# NavCom_Board_3.net
KiCad netlist of a schematic drawn in EAGLE
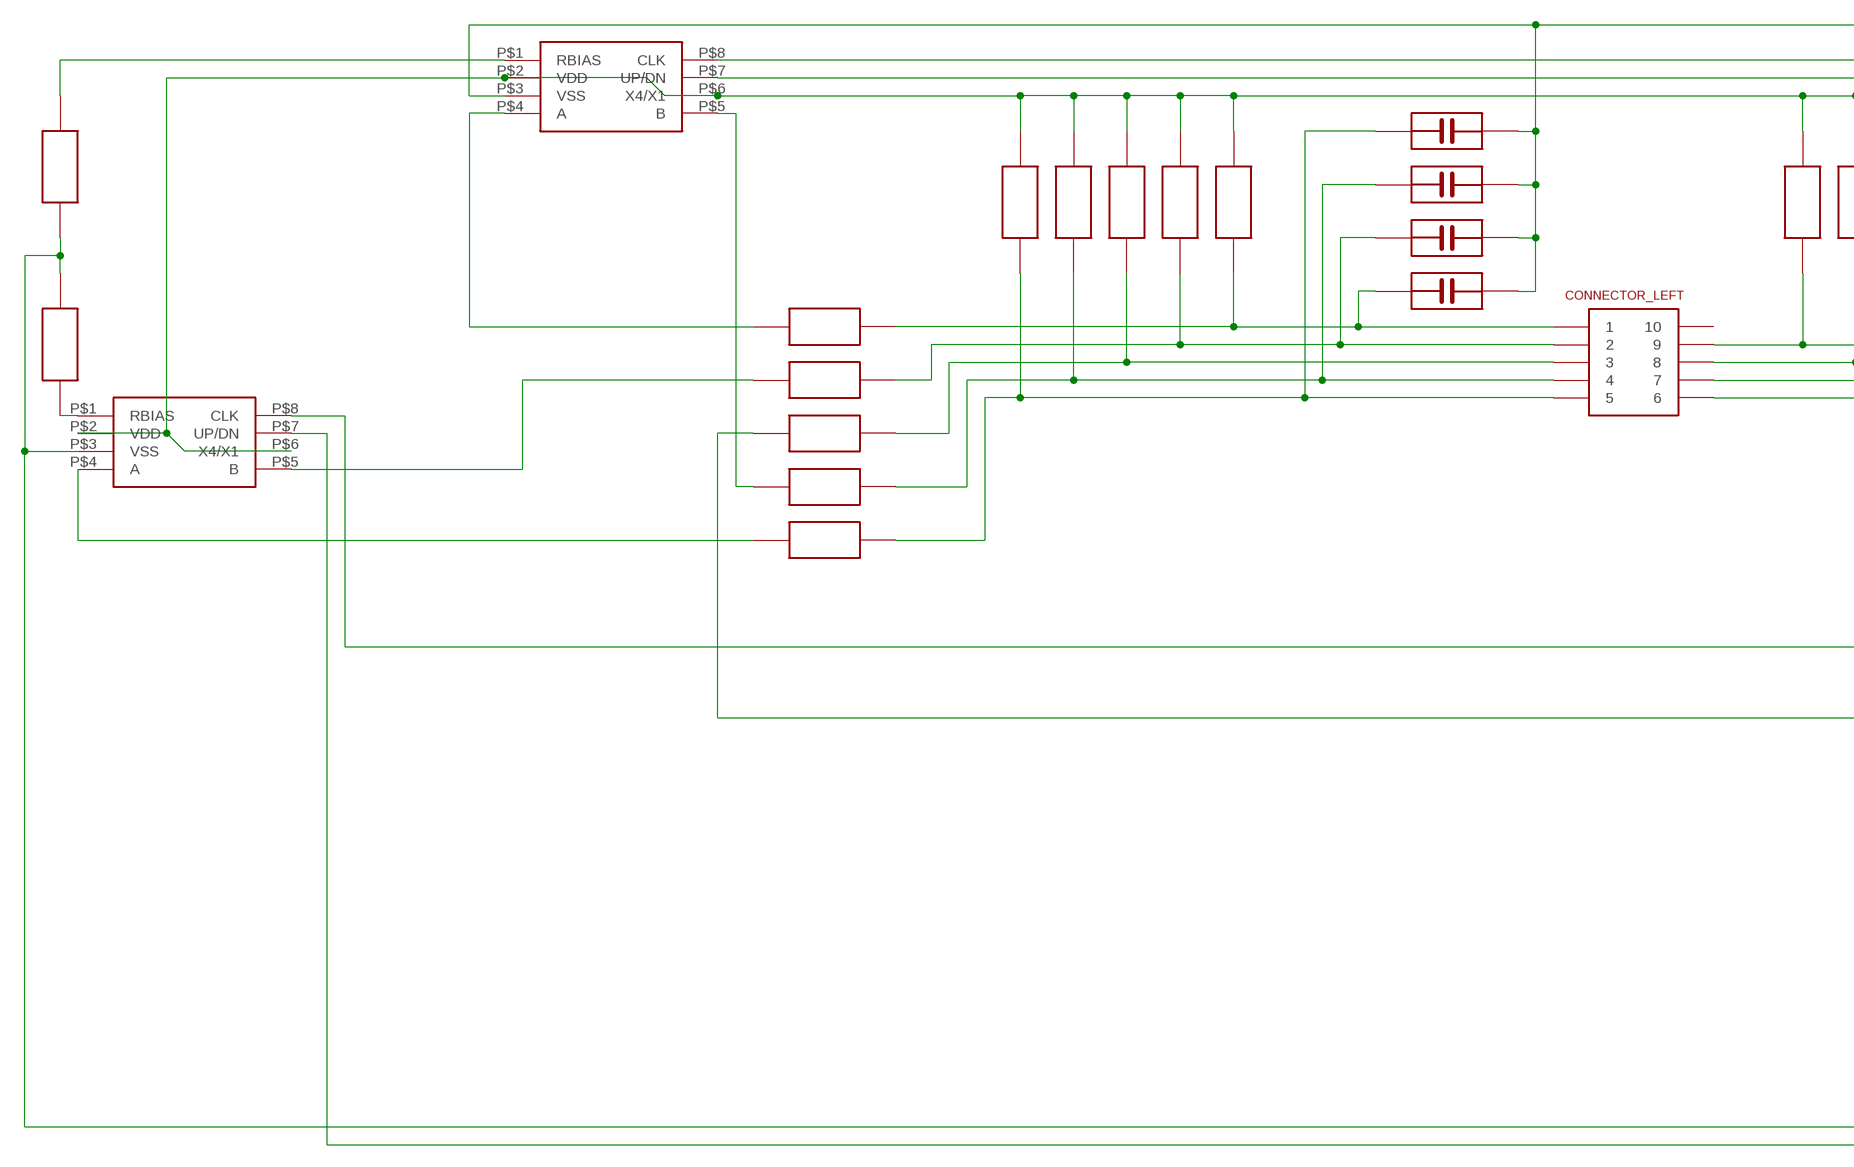
[diagram p0: schematic, sheet 1, part 1 of 2]
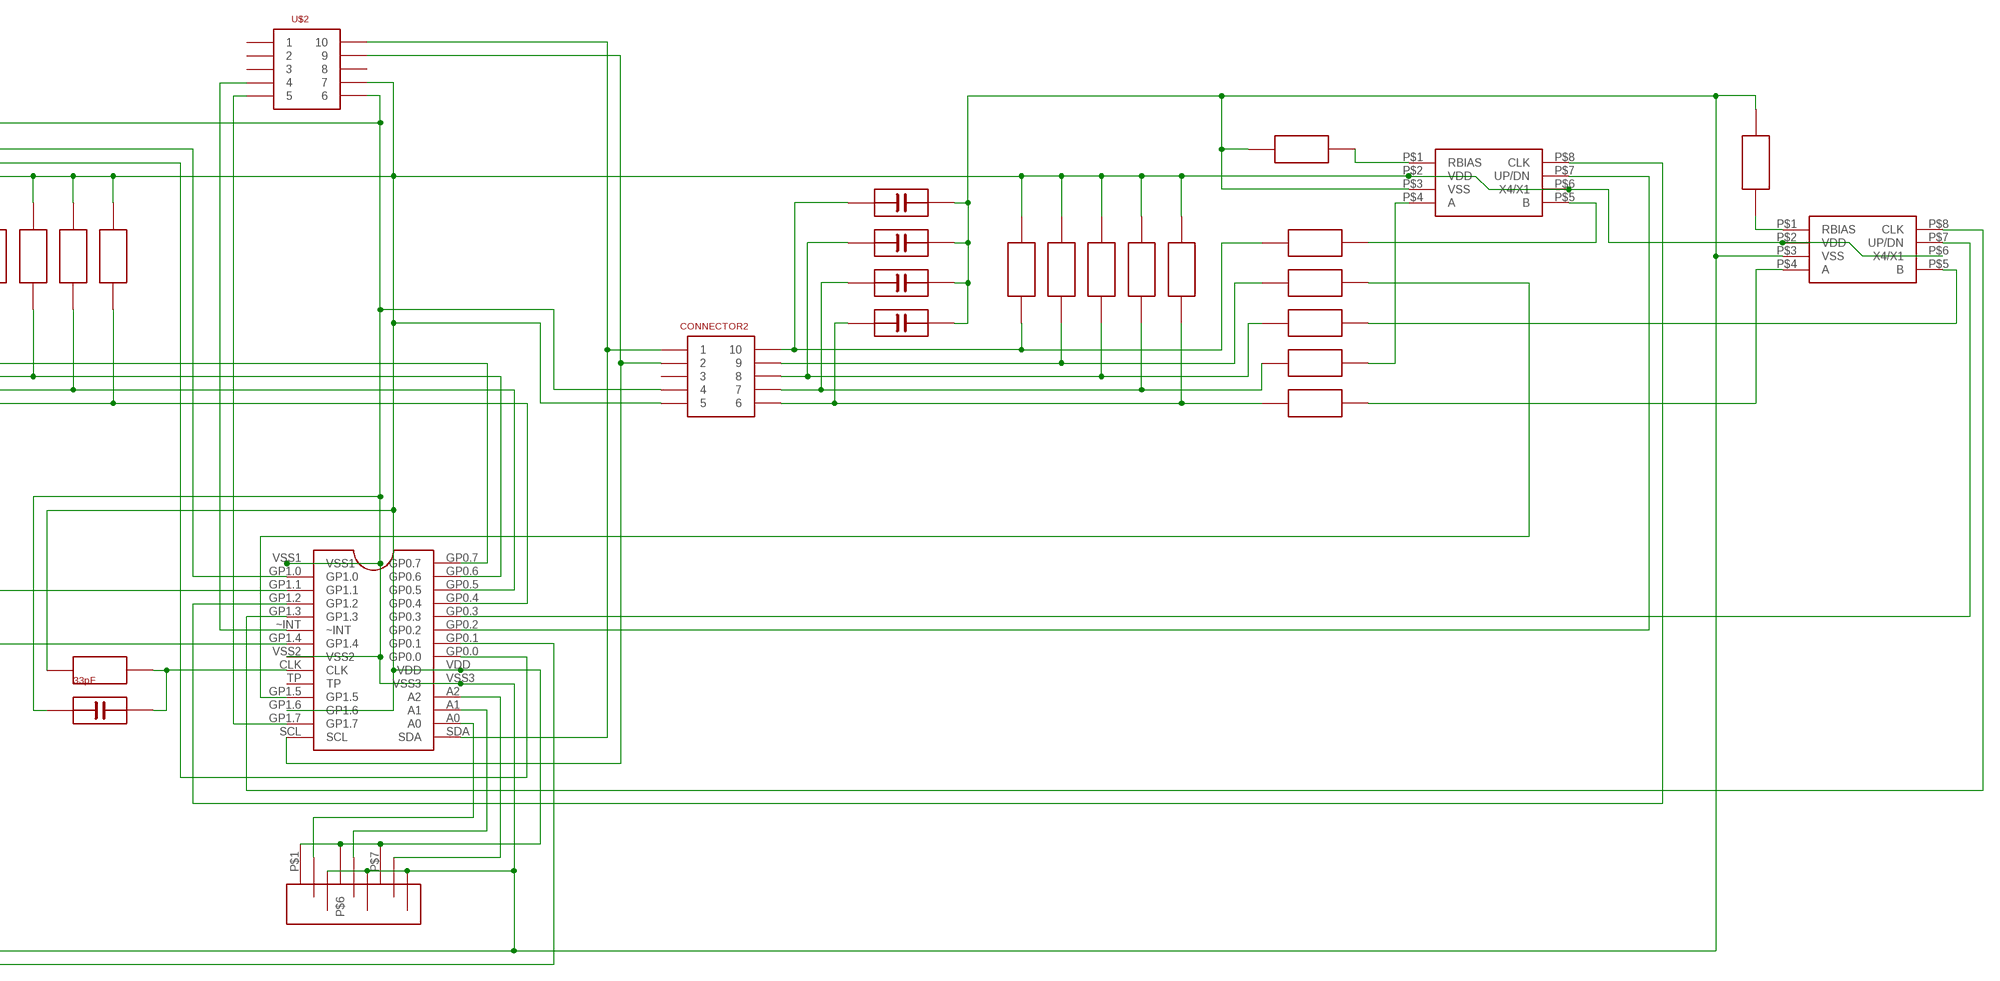
[diagram p1: schematic, sheet 1, part 2 of 2]

(export (version "E")
  (design (tool "Eeschema 10.0.6"))
  (components
    (comp (ref "33PF")
      (value "33pF")
      (footprint "eagle-import:KONDENZATOR")
      (libsource (lib "eagle-import") (part "KONDENZATOR"))
    )
    (comp (ref "CONNECTOR2")
      (value "LISTA_2X5")
      (footprint "eagle-import:LISTA_2X5")
      (libsource (lib "eagle-import") (part "LISTA_2X5"))
    )
    (comp (ref "CONNECTOR_LEFT")
      (value "LISTA_2X5")
      (footprint "eagle-import:LISTA_2X5")
      (libsource (lib "eagle-import") (part "LISTA_2X5"))
    )
    (comp (ref "U$1")
      (value "MCP23016")
      (footprint "eagle-import:MCP23016")
      (libsource (lib "eagle-import") (part "MCP23016"))
    )
    (comp (ref "U$2")
      (value "LISTA_2X5")
      (footprint "eagle-import:LISTA_2X5")
      (libsource (lib "eagle-import") (part "LISTA_2X5"))
    )
    (comp (ref "U$3")
      (value "LS7084")
      (footprint "eagle-import:LS7084")
      (libsource (lib "eagle-import") (part "LS7084"))
    )
    (comp (ref "U$4")
      (value "LS7084")
      (footprint "eagle-import:LS7084")
      (libsource (lib "eagle-import") (part "LS7084"))
    )
    (comp (ref "U$5")
      (value "LS7084")
      (footprint "eagle-import:LS7084")
      (libsource (lib "eagle-import") (part "LS7084"))
    )
    (comp (ref "U$6")
      (value "LS7084")
      (footprint "eagle-import:LS7084")
      (libsource (lib "eagle-import") (part "LS7084"))
    )
    (comp (ref "U$7")
      (value "REZISTOR")
      (footprint "eagle-import:REZISTOR")
      (libsource (lib "eagle-import") (part "REZISTOR"))
    )
    (comp (ref "U$8")
      (value "470Ω")
      (footprint "eagle-import:REZISTOR")
      (libsource (lib "eagle-import") (part "REZISTOR"))
    )
    (comp (ref "U$9")
      (value "REZISTOR")
      (footprint "eagle-import:REZISTOR")
      (libsource (lib "eagle-import") (part "REZISTOR"))
    )
    (comp (ref "U$10")
      (value "REZISTOR")
      (footprint "eagle-import:REZISTOR")
      (libsource (lib "eagle-import") (part "REZISTOR"))
    )
    (comp (ref "U$11")
      (value "ADRESA_0..2")
      (footprint "eagle-import:ADRESA_0..2")
      (libsource (lib "eagle-import") (part "ADRESA_0..2"))
    )
    (comp (ref "U$12")
      (value "470Ω")
      (footprint "eagle-import:REZISTOR")
      (libsource (lib "eagle-import") (part "REZISTOR"))
    )
    (comp (ref "U$13")
      (value "REZISTOR")
      (footprint "eagle-import:REZISTOR")
      (libsource (lib "eagle-import") (part "REZISTOR"))
    )
    (comp (ref "U$14")
      (value "REZISTOR")
      (footprint "eagle-import:REZISTOR")
      (libsource (lib "eagle-import") (part "REZISTOR"))
    )
    (comp (ref "U$15")
      (value "REZISTOR")
      (footprint "eagle-import:REZISTOR")
      (libsource (lib "eagle-import") (part "REZISTOR"))
    )
    (comp (ref "U$16")
      (value "470Ω")
      (footprint "eagle-import:REZISTOR")
      (libsource (lib "eagle-import") (part "REZISTOR"))
    )
    (comp (ref "U$17")
      (value "REZISTOR")
      (footprint "eagle-import:REZISTOR")
      (libsource (lib "eagle-import") (part "REZISTOR"))
    )
    (comp (ref "U$18")
      (value "REZISTOR")
      (footprint "eagle-import:REZISTOR")
      (libsource (lib "eagle-import") (part "REZISTOR"))
    )
    (comp (ref "U$19")
      (value "REZISTOR")
      (footprint "eagle-import:REZISTOR")
      (libsource (lib "eagle-import") (part "REZISTOR"))
    )
    (comp (ref "U$20")
      (value "REZISTOR")
      (footprint "eagle-import:REZISTOR")
      (libsource (lib "eagle-import") (part "REZISTOR"))
    )
    (comp (ref "U$21")
      (value "REZISTOR")
      (footprint "eagle-import:REZISTOR")
      (libsource (lib "eagle-import") (part "REZISTOR"))
    )
    (comp (ref "U$22")
      (value "REZISTOR")
      (footprint "eagle-import:REZISTOR")
      (libsource (lib "eagle-import") (part "REZISTOR"))
    )
    (comp (ref "U$23")
      (value "3.9k")
      (footprint "eagle-import:REZISTOR")
      (libsource (lib "eagle-import") (part "REZISTOR"))
    )
    (comp (ref "U$24")
      (value "103")
      (footprint "eagle-import:KONDENZATOR")
      (libsource (lib "eagle-import") (part "KONDENZATOR"))
    )
    (comp (ref "U$25")
      (value "KONDENZATOR")
      (footprint "eagle-import:KONDENZATOR")
      (libsource (lib "eagle-import") (part "KONDENZATOR"))
    )
    (comp (ref "U$26")
      (value "KONDENZATOR")
      (footprint "eagle-import:KONDENZATOR")
      (libsource (lib "eagle-import") (part "KONDENZATOR"))
    )
    (comp (ref "U$27")
      (value "470M")
      (footprint "eagle-import:REZISTOR")
      (libsource (lib "eagle-import") (part "REZISTOR"))
    )
    (comp (ref "U$28")
      (value "KONDENZATOR")
      (footprint "eagle-import:KONDENZATOR")
      (libsource (lib "eagle-import") (part "KONDENZATOR"))
    )
    (comp (ref "U$29")
      (value "4.7k")
      (footprint "eagle-import:REZISTOR")
      (libsource (lib "eagle-import") (part "REZISTOR"))
    )
    (comp (ref "U$30")
      (value "REZISTOR")
      (footprint "eagle-import:REZISTOR")
      (libsource (lib "eagle-import") (part "REZISTOR"))
    )
    (comp (ref "U$31")
      (value "REZISTOR")
      (footprint "eagle-import:REZISTOR")
      (libsource (lib "eagle-import") (part "REZISTOR"))
    )
    (comp (ref "U$32")
      (value "REZISTOR")
      (footprint "eagle-import:REZISTOR")
      (libsource (lib "eagle-import") (part "REZISTOR"))
    )
    (comp (ref "U$33")
      (value "REZISTOR")
      (footprint "eagle-import:REZISTOR")
      (libsource (lib "eagle-import") (part "REZISTOR"))
    )
    (comp (ref "U$34")
      (value "470M")
      (footprint "eagle-import:REZISTOR")
      (libsource (lib "eagle-import") (part "REZISTOR"))
    )
    (comp (ref "U$35")
      (value "4.7k")
      (footprint "eagle-import:REZISTOR")
      (libsource (lib "eagle-import") (part "REZISTOR"))
    )
    (comp (ref "U$36")
      (value "REZISTOR")
      (footprint "eagle-import:REZISTOR")
      (libsource (lib "eagle-import") (part "REZISTOR"))
    )
    (comp (ref "U$37")
      (value "KONDENZATOR")
      (footprint "eagle-import:KONDENZATOR")
      (libsource (lib "eagle-import") (part "KONDENZATOR"))
    )
    (comp (ref "U$38")
      (value "REZISTOR")
      (footprint "eagle-import:REZISTOR")
      (libsource (lib "eagle-import") (part "REZISTOR"))
    )
    (comp (ref "U$39")
      (value "REZISTOR")
      (footprint "eagle-import:REZISTOR")
      (libsource (lib "eagle-import") (part "REZISTOR"))
    )
    (comp (ref "U$40")
      (value "470M")
      (footprint "eagle-import:REZISTOR")
      (libsource (lib "eagle-import") (part "REZISTOR"))
    )
    (comp (ref "U$41")
      (value "470M")
      (footprint "eagle-import:REZISTOR")
      (libsource (lib "eagle-import") (part "REZISTOR"))
    )
    (comp (ref "U$42")
      (value "KONDENZATOR")
      (footprint "eagle-import:KONDENZATOR")
      (libsource (lib "eagle-import") (part "KONDENZATOR"))
    )
    (comp (ref "U$43")
      (value "KONDENZATOR")
      (footprint "eagle-import:KONDENZATOR")
      (libsource (lib "eagle-import") (part "KONDENZATOR"))
    )
    (comp (ref "U$44")
      (value "103")
      (footprint "eagle-import:KONDENZATOR")
      (libsource (lib "eagle-import") (part "KONDENZATOR"))
    )
  )
  (nets
    (net (code "1") (name "Net-(33PF-PadP$2)") (class "Default")
      (node (ref "33PF") (pin "P$2") (pinfunction "P$2_P$2") (pintype "bidirectional"))
      (node (ref "U$1") (pin "CLK") (pinfunction "CLK_CLK") (pintype "bidirectional"))
      (node (ref "U$23") (pin "P$2") (pinfunction "P$2_P$2") (pintype "bidirectional"))
    )
    (net (code "2") (name "Net-(CONNECTOR2-Pad1)") (class "Default")
      (node (ref "CONNECTOR2") (pin "1") (pinfunction "1_1") (pintype "bidirectional"))
      (node (ref "U$1") (pin "SDA") (pinfunction "SDA_SDA") (pintype "bidirectional"))
      (node (ref "U$2") (pin "10") (pinfunction "10_10") (pintype "bidirectional"))
    )
    (net (code "3") (name "Net-(CONNECTOR2-Pad2)") (class "Default")
      (node (ref "CONNECTOR2") (pin "2") (pinfunction "2_2") (pintype "bidirectional"))
      (node (ref "U$1") (pin "SCL") (pinfunction "SCL_SCL") (pintype "bidirectional"))
      (node (ref "U$2") (pin "9") (pinfunction "9_9") (pintype "bidirectional"))
    )
    (net (code "4") (name "Net-(CONNECTOR2-Pad6)") (class "Default")
      (node (ref "CONNECTOR2") (pin "6") (pinfunction "6_6") (pintype "bidirectional"))
      (node (ref "U$12") (pin "P$1") (pinfunction "P$1_P$1") (pintype "bidirectional"))
      (node (ref "U$33") (pin "P$2") (pinfunction "P$2_P$2") (pintype "bidirectional"))
      (node (ref "U$44") (pin "P$1") (pinfunction "P$1_P$1") (pintype "bidirectional"))
    )
    (net (code "5") (name "Net-(CONNECTOR2-Pad7)") (class "Default")
      (node (ref "CONNECTOR2") (pin "7") (pinfunction "7_7") (pintype "bidirectional"))
      (node (ref "U$17") (pin "P$1") (pinfunction "P$1_P$1") (pintype "bidirectional"))
      (node (ref "U$32") (pin "P$2") (pinfunction "P$2_P$2") (pintype "bidirectional"))
      (node (ref "U$43") (pin "P$1") (pinfunction "P$1_P$1") (pintype "bidirectional"))
    )
    (net (code "6") (name "Net-(CONNECTOR2-Pad8)") (class "Default")
      (node (ref "CONNECTOR2") (pin "8") (pinfunction "8_8") (pintype "bidirectional"))
      (node (ref "U$10") (pin "P$1") (pinfunction "P$1_P$1") (pintype "bidirectional"))
      (node (ref "U$31") (pin "P$2") (pinfunction "P$2_P$2") (pintype "bidirectional"))
      (node (ref "U$42") (pin "P$1") (pinfunction "P$1_P$1") (pintype "bidirectional"))
    )
    (net (code "7") (name "Net-(CONNECTOR2-Pad9)") (class "Default")
      (node (ref "CONNECTOR2") (pin "9") (pinfunction "9_9") (pintype "bidirectional"))
      (node (ref "U$30") (pin "P$2") (pinfunction "P$2_P$2") (pintype "bidirectional"))
      (node (ref "U$9") (pin "P$1") (pinfunction "P$1_P$1") (pintype "bidirectional"))
    )
    (net (code "8") (name "Net-(CONNECTOR2-Pad10)") (class "Default")
      (node (ref "CONNECTOR2") (pin "10") (pinfunction "10_10") (pintype "bidirectional"))
      (node (ref "U$29") (pin "P$2") (pinfunction "P$2_P$2") (pintype "bidirectional"))
      (node (ref "U$37") (pin "P$1") (pinfunction "P$1_P$1") (pintype "bidirectional"))
      (node (ref "U$7") (pin "P$1") (pinfunction "P$1_P$1") (pintype "bidirectional"))
    )
    (net (code "9") (name "Net-(CONNECTOR_LEFT-Pad1)") (class "Default")
      (node (ref "CONNECTOR_LEFT") (pin "1") (pinfunction "1_1") (pintype "bidirectional"))
      (node (ref "U$16") (pin "P$2") (pinfunction "P$2_P$2") (pintype "bidirectional"))
      (node (ref "U$24") (pin "P$1") (pinfunction "P$1_P$1") (pintype "bidirectional"))
      (node (ref "U$35") (pin "P$2") (pinfunction "P$2_P$2") (pintype "bidirectional"))
    )
    (net (code "10") (name "Net-(CONNECTOR_LEFT-Pad2)") (class "Default")
      (node (ref "CONNECTOR_LEFT") (pin "2") (pinfunction "2_2") (pintype "bidirectional"))
      (node (ref "U$13") (pin "P$2") (pinfunction "P$2_P$2") (pintype "bidirectional"))
      (node (ref "U$25") (pin "P$1") (pinfunction "P$1_P$1") (pintype "bidirectional"))
      (node (ref "U$36") (pin "P$2") (pinfunction "P$2_P$2") (pintype "bidirectional"))
    )
    (net (code "11") (name "Net-(CONNECTOR_LEFT-Pad3)") (class "Default")
      (node (ref "CONNECTOR_LEFT") (pin "3") (pinfunction "3_3") (pintype "bidirectional"))
      (node (ref "U$14") (pin "P$2") (pinfunction "P$2_P$2") (pintype "bidirectional"))
      (node (ref "U$22") (pin "P$2") (pinfunction "P$2_P$2") (pintype "bidirectional"))
    )
    (net (code "12") (name "Net-(CONNECTOR_LEFT-Pad4)") (class "Default")
      (node (ref "CONNECTOR_LEFT") (pin "4") (pinfunction "4_4") (pintype "bidirectional"))
      (node (ref "U$15") (pin "P$2") (pinfunction "P$2_P$2") (pintype "bidirectional"))
      (node (ref "U$26") (pin "P$1") (pinfunction "P$1_P$1") (pintype "bidirectional"))
      (node (ref "U$38") (pin "P$2") (pinfunction "P$2_P$2") (pintype "bidirectional"))
    )
    (net (code "13") (name "Net-(CONNECTOR_LEFT-Pad5)") (class "Default")
      (node (ref "CONNECTOR_LEFT") (pin "5") (pinfunction "5_5") (pintype "bidirectional"))
      (node (ref "U$18") (pin "P$2") (pinfunction "P$2_P$2") (pintype "bidirectional"))
      (node (ref "U$28") (pin "P$1") (pinfunction "P$1_P$1") (pintype "bidirectional"))
      (node (ref "U$39") (pin "P$2") (pinfunction "P$2_P$2") (pintype "bidirectional"))
    )
    (net (code "14") (name "Net-(CONNECTOR_LEFT-Pad6)") (class "Default")
      (node (ref "CONNECTOR_LEFT") (pin "6") (pinfunction "6_6") (pintype "bidirectional"))
      (node (ref "U$1") (pin "GP0.4") (pinfunction "GP0.4_GP0.4") (pintype "bidirectional"))
      (node (ref "U$21") (pin "P$2") (pinfunction "P$2_P$2") (pintype "bidirectional"))
    )
    (net (code "15") (name "Net-(CONNECTOR_LEFT-Pad7)") (class "Default")
      (node (ref "CONNECTOR_LEFT") (pin "7") (pinfunction "7_7") (pintype "bidirectional"))
      (node (ref "U$1") (pin "GP0.5") (pinfunction "GP0.5_GP0.5") (pintype "bidirectional"))
      (node (ref "U$20") (pin "P$2") (pinfunction "P$2_P$2") (pintype "bidirectional"))
    )
    (net (code "16") (name "Net-(CONNECTOR_LEFT-Pad8)") (class "Default")
      (node (ref "CONNECTOR_LEFT") (pin "8") (pinfunction "8_8") (pintype "bidirectional"))
      (node (ref "U$1") (pin "GP0.6") (pinfunction "GP0.6_GP0.6") (pintype "bidirectional"))
      (node (ref "U$19") (pin "P$2") (pinfunction "P$2_P$2") (pintype "bidirectional"))
    )
    (net (code "17") (name "Net-(CONNECTOR_LEFT-Pad9)") (class "Default")
      (node (ref "CONNECTOR_LEFT") (pin "9") (pinfunction "9_9") (pintype "bidirectional"))
      (node (ref "U$1") (pin "GP0.7") (pinfunction "GP0.7_GP0.7") (pintype "bidirectional"))
      (node (ref "U$8") (pin "P$2") (pinfunction "P$2_P$2") (pintype "bidirectional"))
    )
    (net (code "18") (name "Net-(U$1-PadA0)") (class "Default")
      (node (ref "U$1") (pin "A0") (pinfunction "A0_A0") (pintype "bidirectional"))
      (node (ref "U$11") (pin "P$2") (pinfunction "P$2_P$2") (pintype "bidirectional"))
    )
    (net (code "19") (name "Net-(U$1-PadA1)") (class "Default")
      (node (ref "U$1") (pin "A1") (pinfunction "A1_A1") (pintype "bidirectional"))
      (node (ref "U$11") (pin "P$5") (pinfunction "P$5_P$5") (pintype "bidirectional"))
    )
    (net (code "20") (name "Net-(U$1-PadA2)") (class "Default")
      (node (ref "U$1") (pin "A2") (pinfunction "A2_A2") (pintype "bidirectional"))
      (node (ref "U$11") (pin "P$8") (pinfunction "P$8_P$8") (pintype "bidirectional"))
    )
    (net (code "21") (name "Net-(U$1-PadGP1.4)") (class "Default")
      (node (ref "U$1") (pin "GP1.4") (pinfunction "GP1.4_GP1.4") (pintype "bidirectional"))
      (node (ref "U$22") (pin "P$1") (pinfunction "P$1_P$1") (pintype "bidirectional"))
    )
    (net (code "22") (name "Net-(U$1-PadGP1.5)") (class "Default")
      (node (ref "U$1") (pin "GP1.5") (pinfunction "GP1.5_GP1.5") (pintype "bidirectional"))
      (node (ref "U$30") (pin "P$1") (pinfunction "P$1_P$1") (pintype "bidirectional"))
    )
    (net (code "23") (name "Net-(U$1-PadGP1.7)") (class "Default")
      (node (ref "U$1") (pin "GP1.7") (pinfunction "GP1.7_GP1.7") (pintype "bidirectional"))
      (node (ref "U$2") (pin "5") (pinfunction "5_5") (pintype "bidirectional"))
    )
    (net (code "24") (name "Net-(U$1-~{INT})") (class "Default")
      (node (ref "U$1") (pin "~INT") (pinfunction "~{INT}_~INT") (pintype "bidirectional"))
      (node (ref "U$2") (pin "4") (pinfunction "4_4") (pintype "bidirectional"))
    )
    (net (code "25") (name "Net-(U$3-A)") (class "Default")
      (node (ref "U$3") (pin "P$4") (pinfunction "A_P$4") (pintype "bidirectional"))
      (node (ref "U$35") (pin "P$1") (pinfunction "P$1_P$1") (pintype "bidirectional"))
    )
    (net (code "26") (name "Net-(U$3-B)") (class "Default")
      (node (ref "U$3") (pin "P$5") (pinfunction "B_P$5") (pintype "bidirectional"))
      (node (ref "U$38") (pin "P$1") (pinfunction "P$1_P$1") (pintype "bidirectional"))
    )
    (net (code "27") (name "Net-(U$3-CLK)") (class "Default")
      (node (ref "U$1") (pin "GP1.0") (pinfunction "GP1.0_GP1.0") (pintype "bidirectional"))
      (node (ref "U$3") (pin "P$8") (pinfunction "CLK_P$8") (pintype "bidirectional"))
    )
    (net (code "28") (name "Net-(U$3-RBIAS)") (class "Default")
      (node (ref "U$3") (pin "P$1") (pinfunction "RBIAS_P$1") (pintype "bidirectional"))
      (node (ref "U$40") (pin "P$2") (pinfunction "P$2_P$2") (pintype "bidirectional"))
    )
    (net (code "29") (name "Net-(U$3-UP{slash}DN)") (class "Default")
      (node (ref "U$1") (pin "GP0.0") (pinfunction "GP0.0_GP0.0") (pintype "bidirectional"))
      (node (ref "U$3") (pin "P$7") (pinfunction "UP/DN_P$7") (pintype "bidirectional"))
    )
    (net (code "30") (name "Net-(U$3-VDD)") (class "Default")
      (node (ref "CONNECTOR2") (pin "5") (pinfunction "5_5") (pintype "bidirectional"))
      (node (ref "U$1") (pin "GP1.6") (pinfunction "GP1.6_GP1.6") (pintype "bidirectional"))
      (node (ref "U$1") (pin "VDD") (pinfunction "VDD_VDD") (pintype "bidirectional"))
      (node (ref "U$10") (pin "P$2") (pinfunction "P$2_P$2") (pintype "bidirectional"))
      (node (ref "U$11") (pin "P$1") (pinfunction "P$1_P$1") (pintype "bidirectional"))
      (node (ref "U$11") (pin "P$6") (pinfunction "P$6_P$6") (pintype "bidirectional"))
      (node (ref "U$11") (pin "P$7") (pinfunction "P$7_P$7") (pintype "bidirectional"))
      (node (ref "U$12") (pin "P$2") (pinfunction "P$2_P$2") (pintype "bidirectional"))
      (node (ref "U$13") (pin "P$1") (pinfunction "P$1_P$1") (pintype "bidirectional"))
      (node (ref "U$14") (pin "P$1") (pinfunction "P$1_P$1") (pintype "bidirectional"))
      (node (ref "U$15") (pin "P$1") (pinfunction "P$1_P$1") (pintype "bidirectional"))
      (node (ref "U$16") (pin "P$1") (pinfunction "P$1_P$1") (pintype "bidirectional"))
      (node (ref "U$17") (pin "P$2") (pinfunction "P$2_P$2") (pintype "bidirectional"))
      (node (ref "U$18") (pin "P$1") (pinfunction "P$1_P$1") (pintype "bidirectional"))
      (node (ref "U$19") (pin "P$1") (pinfunction "P$1_P$1") (pintype "bidirectional"))
      (node (ref "U$2") (pin "7") (pinfunction "7_7") (pintype "bidirectional"))
      (node (ref "U$20") (pin "P$1") (pinfunction "P$1_P$1") (pintype "bidirectional"))
      (node (ref "U$21") (pin "P$1") (pinfunction "P$1_P$1") (pintype "bidirectional"))
      (node (ref "U$23") (pin "P$1") (pinfunction "P$1_P$1") (pintype "bidirectional"))
      (node (ref "U$3") (pin "P$2") (pinfunction "VDD_P$2") (pintype "bidirectional"))
      (node (ref "U$3") (pin "P$6") (pinfunction "X4/X1_P$6") (pintype "bidirectional"))
      (node (ref "U$4") (pin "P$2") (pinfunction "VDD_P$2") (pintype "bidirectional"))
      (node (ref "U$4") (pin "P$6") (pinfunction "X4/X1_P$6") (pintype "bidirectional"))
      (node (ref "U$5") (pin "P$2") (pinfunction "VDD_P$2") (pintype "bidirectional"))
      (node (ref "U$5") (pin "P$6") (pinfunction "X4/X1_P$6") (pintype "bidirectional"))
      (node (ref "U$6") (pin "P$2") (pinfunction "VDD_P$2") (pintype "bidirectional"))
      (node (ref "U$6") (pin "P$6") (pinfunction "X4/X1_P$6") (pintype "bidirectional"))
      (node (ref "U$7") (pin "P$2") (pinfunction "P$2_P$2") (pintype "bidirectional"))
      (node (ref "U$8") (pin "P$1") (pinfunction "P$1_P$1") (pintype "bidirectional"))
      (node (ref "U$9") (pin "P$2") (pinfunction "P$2_P$2") (pintype "bidirectional"))
    )
    (net (code "31") (name "Net-(U$3-VSS)") (class "Default")
      (node (ref "33PF") (pin "P$1") (pinfunction "P$1_P$1") (pintype "bidirectional"))
      (node (ref "CONNECTOR2") (pin "4") (pinfunction "4_4") (pintype "bidirectional"))
      (node (ref "U$1") (pin "VSS1") (pinfunction "VSS1_VSS1") (pintype "bidirectional"))
      (node (ref "U$1") (pin "VSS2") (pinfunction "VSS2_VSS2") (pintype "bidirectional"))
      (node (ref "U$1") (pin "VSS3") (pinfunction "VSS3_VSS3") (pintype "bidirectional"))
      (node (ref "U$11") (pin "P$3") (pinfunction "P$3_P$3") (pintype "bidirectional"))
      (node (ref "U$11") (pin "P$4") (pinfunction "P$4_P$4") (pintype "bidirectional"))
      (node (ref "U$11") (pin "P$9") (pinfunction "P$9_P$9") (pintype "bidirectional"))
      (node (ref "U$2") (pin "6") (pinfunction "6_6") (pintype "bidirectional"))
      (node (ref "U$24") (pin "P$2") (pinfunction "P$2_P$2") (pintype "bidirectional"))
      (node (ref "U$25") (pin "P$2") (pinfunction "P$2_P$2") (pintype "bidirectional"))
      (node (ref "U$26") (pin "P$2") (pinfunction "P$2_P$2") (pintype "bidirectional"))
      (node (ref "U$27") (pin "P$2") (pinfunction "P$2_P$2") (pintype "bidirectional"))
      (node (ref "U$28") (pin "P$2") (pinfunction "P$2_P$2") (pintype "bidirectional"))
      (node (ref "U$3") (pin "P$3") (pinfunction "VSS_P$3") (pintype "bidirectional"))
      (node (ref "U$34") (pin "P$1") (pinfunction "P$1_P$1") (pintype "bidirectional"))
      (node (ref "U$37") (pin "P$2") (pinfunction "P$2_P$2") (pintype "bidirectional"))
      (node (ref "U$4") (pin "P$3") (pinfunction "VSS_P$3") (pintype "bidirectional"))
      (node (ref "U$40") (pin "P$1") (pinfunction "P$1_P$1") (pintype "bidirectional"))
      (node (ref "U$41") (pin "P$1") (pinfunction "P$1_P$1") (pintype "bidirectional"))
      (node (ref "U$42") (pin "P$2") (pinfunction "P$2_P$2") (pintype "bidirectional"))
      (node (ref "U$43") (pin "P$2") (pinfunction "P$2_P$2") (pintype "bidirectional"))
      (node (ref "U$44") (pin "P$2") (pinfunction "P$2_P$2") (pintype "bidirectional"))
      (node (ref "U$5") (pin "P$3") (pinfunction "VSS_P$3") (pintype "bidirectional"))
      (node (ref "U$6") (pin "P$3") (pinfunction "VSS_P$3") (pintype "bidirectional"))
    )
    (net (code "32") (name "Net-(U$4-A)") (class "Default")
      (node (ref "U$32") (pin "P$1") (pinfunction "P$1_P$1") (pintype "bidirectional"))
      (node (ref "U$4") (pin "P$4") (pinfunction "A_P$4") (pintype "bidirectional"))
    )
    (net (code "33") (name "Net-(U$4-B)") (class "Default")
      (node (ref "U$29") (pin "P$1") (pinfunction "P$1_P$1") (pintype "bidirectional"))
      (node (ref "U$4") (pin "P$5") (pinfunction "B_P$5") (pintype "bidirectional"))
    )
    (net (code "34") (name "Net-(U$4-CLK)") (class "Default")
      (node (ref "U$1") (pin "GP1.2") (pinfunction "GP1.2_GP1.2") (pintype "bidirectional"))
      (node (ref "U$4") (pin "P$8") (pinfunction "CLK_P$8") (pintype "bidirectional"))
    )
    (net (code "35") (name "Net-(U$4-RBIAS)") (class "Default")
      (node (ref "U$27") (pin "P$1") (pinfunction "P$1_P$1") (pintype "bidirectional"))
      (node (ref "U$4") (pin "P$1") (pinfunction "RBIAS_P$1") (pintype "bidirectional"))
    )
    (net (code "36") (name "Net-(U$4-UP{slash}DN)") (class "Default")
      (node (ref "U$1") (pin "GP0.2") (pinfunction "GP0.2_GP0.2") (pintype "bidirectional"))
      (node (ref "U$4") (pin "P$7") (pinfunction "UP/DN_P$7") (pintype "bidirectional"))
    )
    (net (code "37") (name "Net-(U$5-A)") (class "Default")
      (node (ref "U$33") (pin "P$1") (pinfunction "P$1_P$1") (pintype "bidirectional"))
      (node (ref "U$5") (pin "P$4") (pinfunction "A_P$4") (pintype "bidirectional"))
    )
    (net (code "38") (name "Net-(U$5-B)") (class "Default")
      (node (ref "U$31") (pin "P$1") (pinfunction "P$1_P$1") (pintype "bidirectional"))
      (node (ref "U$5") (pin "P$5") (pinfunction "B_P$5") (pintype "bidirectional"))
    )
    (net (code "39") (name "Net-(U$5-CLK)") (class "Default")
      (node (ref "U$1") (pin "GP1.3") (pinfunction "GP1.3_GP1.3") (pintype "bidirectional"))
      (node (ref "U$5") (pin "P$8") (pinfunction "CLK_P$8") (pintype "bidirectional"))
    )
    (net (code "40") (name "Net-(U$5-RBIAS)") (class "Default")
      (node (ref "U$34") (pin "P$2") (pinfunction "P$2_P$2") (pintype "bidirectional"))
      (node (ref "U$5") (pin "P$1") (pinfunction "RBIAS_P$1") (pintype "bidirectional"))
    )
    (net (code "41") (name "Net-(U$5-UP{slash}DN)") (class "Default")
      (node (ref "U$1") (pin "GP0.3") (pinfunction "GP0.3_GP0.3") (pintype "bidirectional"))
      (node (ref "U$5") (pin "P$7") (pinfunction "UP/DN_P$7") (pintype "bidirectional"))
    )
    (net (code "42") (name "Net-(U$6-A)") (class "Default")
      (node (ref "U$39") (pin "P$1") (pinfunction "P$1_P$1") (pintype "bidirectional"))
      (node (ref "U$6") (pin "P$4") (pinfunction "A_P$4") (pintype "bidirectional"))
    )
    (net (code "43") (name "Net-(U$6-B)") (class "Default")
      (node (ref "U$36") (pin "P$1") (pinfunction "P$1_P$1") (pintype "bidirectional"))
      (node (ref "U$6") (pin "P$5") (pinfunction "B_P$5") (pintype "bidirectional"))
    )
    (net (code "44") (name "Net-(U$6-CLK)") (class "Default")
      (node (ref "U$1") (pin "GP1.1") (pinfunction "GP1.1_GP1.1") (pintype "bidirectional"))
      (node (ref "U$6") (pin "P$8") (pinfunction "CLK_P$8") (pintype "bidirectional"))
    )
    (net (code "45") (name "Net-(U$6-RBIAS)") (class "Default")
      (node (ref "U$41") (pin "P$2") (pinfunction "P$2_P$2") (pintype "bidirectional"))
      (node (ref "U$6") (pin "P$1") (pinfunction "RBIAS_P$1") (pintype "bidirectional"))
    )
    (net (code "46") (name "Net-(U$6-UP{slash}DN)") (class "Default")
      (node (ref "U$1") (pin "GP0.1") (pinfunction "GP0.1_GP0.1") (pintype "bidirectional"))
      (node (ref "U$6") (pin "P$7") (pinfunction "UP/DN_P$7") (pintype "bidirectional"))
    )
    (net (code "47") (name "unconnected-(CONNECTOR2-Pad3)") (class "Default")
      (node (ref "CONNECTOR2") (pin "3") (pinfunction "3_3") (pintype "bidirectional"))
    )
    (net (code "48") (name "unconnected-(CONNECTOR_LEFT-Pad10)") (class "Default")
      (node (ref "CONNECTOR_LEFT") (pin "10") (pinfunction "10_10") (pintype "bidirectional"))
    )
    (net (code "49") (name "unconnected-(U$1-PadTP)") (class "Default")
      (node (ref "U$1") (pin "TP") (pinfunction "TP_TP") (pintype "bidirectional"))
    )
    (net (code "50") (name "unconnected-(U$2-Pad1)") (class "Default")
      (node (ref "U$2") (pin "1") (pinfunction "1_1") (pintype "bidirectional"))
    )
    (net (code "51") (name "unconnected-(U$2-Pad2)") (class "Default")
      (node (ref "U$2") (pin "2") (pinfunction "2_2") (pintype "bidirectional"))
    )
    (net (code "52") (name "unconnected-(U$2-Pad3)") (class "Default")
      (node (ref "U$2") (pin "3") (pinfunction "3_3") (pintype "bidirectional"))
    )
    (net (code "53") (name "unconnected-(U$2-Pad8)") (class "Default")
      (node (ref "U$2") (pin "8") (pinfunction "8_8") (pintype "bidirectional"))
    )
  )
)
